# 012_AdditionalFunction.net
KiCad netlist of a schematic drawn in Altium Designer
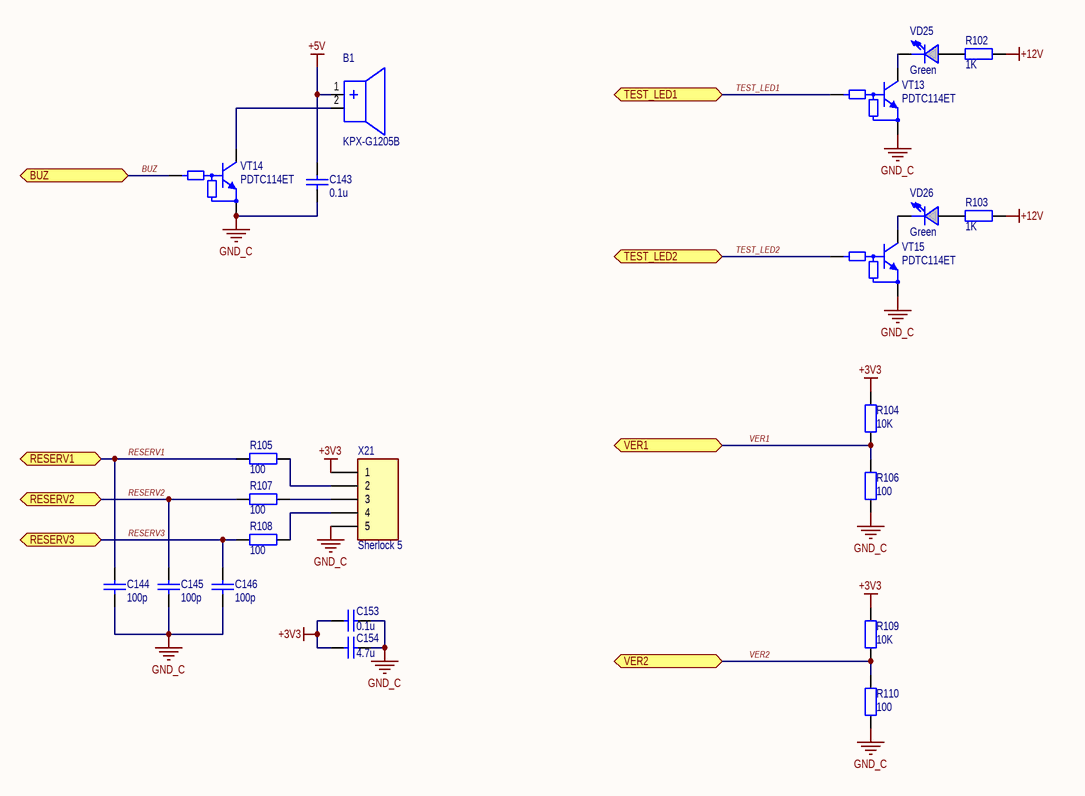
[diagram p0: 012_AdditionalFunction.SchDoc]

(export (version "E")
  (design (tool "Eeschema 10.0.6"))
  (components
    (comp (ref "B1")
      (value "KPX-G1205B")
      (footprint "mainLib:KPX-G12")
      (description "Magnetic Buzzer")
      (fields (field (name "MANUFACTURER") "KEPO"))
      (libsource (lib "mainLib") (part "KPX-G1205B"))
    )
    (comp (ref "C143")
      (value "0.1u")
      (footprint "mainLib:SMD_C_0603")
      (description "SMD C 0603 MURATA 50V 10% X7R")
      (fields (field (name "PARTNUMBER") "GRM188R71H104K") (field (name "MANUFACTURER") "MURATA"))
      (libsource (lib "mainRCLib") (part "C0603 0.1u 50V 10%"))
    )
    (comp (ref "C144")
      (value "100p")
      (footprint "mainLib:SMD_C_0603")
      (description "SMD C 0603 MURATA 100V 5% NP0")
      (fields (field (name "PARTNUMBER") "GRM1885C2A101JA01") (field (name "MANUFACTURER") "MURATA"))
      (libsource (lib "mainRCLib") (part "C0603 100p 100V 5%"))
    )
    (comp (ref "C145")
      (value "100p")
      (footprint "mainLib:SMD_C_0603")
      (description "SMD C 0603 MURATA 100V 5% NP0")
      (fields (field (name "PARTNUMBER") "GRM1885C2A101JA01") (field (name "MANUFACTURER") "MURATA"))
      (libsource (lib "mainRCLib") (part "C0603 100p 100V 5%"))
    )
    (comp (ref "C146")
      (value "100p")
      (footprint "mainLib:SMD_C_0603")
      (description "SMD C 0603 MURATA 100V 5% NP0")
      (fields (field (name "PARTNUMBER") "GRM1885C2A101JA01") (field (name "MANUFACTURER") "MURATA"))
      (libsource (lib "mainRCLib") (part "C0603 100p 100V 5%"))
    )
    (comp (ref "C153")
      (value "0.1u")
      (footprint "mainLib:SMD_C_0603")
      (description "SMD C 0603 MURATA 50V 10% X7R")
      (fields (field (name "PARTNUMBER") "GRM188R71H104K") (field (name "MANUFACTURER") "MURATA"))
      (libsource (lib "mainRCLib") (part "C0603 0.1u 50V 10%"))
    )
    (comp (ref "C154")
      (value "4.7u")
      (footprint "mainLib:SMD_C_0805")
      (description "SMD C 0805 MURATA 50V 5% NP0")
      (fields (field (name "PARTNUMBER") "GRM21BR61E475M") (field (name "MANUFACTURER") "MURATA"))
      (libsource (lib "mainRCLib") (part "C0805 4.7u 25V 20%  X5R"))
    )
    (comp (ref "R102")
      (value "1K")
      (footprint "mainLib:SMD_R_1206")
      (description "SMD R 1206 VISHAY 0.25W 200V 1% 100ppm")
      (fields (field (name "PARTNUMBER") "CRCW12061K00FK") (field (name "MANUFACTURER") "VISHAY"))
      (libsource (lib "mainRCLib") (part "R1206 1K 1%"))
    )
    (comp (ref "R103")
      (value "1K")
      (footprint "mainLib:SMD_R_1206")
      (description "SMD R 1206 VISHAY 0.25W 200V 1% 100ppm")
      (fields (field (name "PARTNUMBER") "CRCW12061K00FK") (field (name "MANUFACTURER") "VISHAY"))
      (libsource (lib "mainRCLib") (part "R1206 1K 1%"))
    )
    (comp (ref "R104")
      (value "10K")
      (footprint "SMD_R_0603")
      (description "SMD R 0603 VISHAY 0.1W 75V 1% 100ppm")
      (fields (field (name "PARTNUMBER") "CRCW060310K0FK") (field (name "MANUFACTURER") "VISHAY"))
      (libsource (lib "mainRCLib") (part "R0603 10К 1%"))
    )
    (comp (ref "R105")
      (value "100")
      (footprint "SMD_R_0603")
      (description "SMD R 0603 VISHAY 0.1W 75V 1% 100ppm")
      (fields (field (name "PARTNUMBER") "CRCW0603100RFK") (field (name "MANUFACTURER") "VISHAY"))
      (libsource (lib "mainRCLib") (part "R0603 100 1%"))
    )
    (comp (ref "R106")
      (value "100")
      (footprint "SMD_R_0603")
      (description "SMD R 0603 VISHAY 0.1W 75V 1% 100ppm")
      (fields (field (name "PARTNUMBER") "CRCW0603100RFK") (field (name "MANUFACTURER") "VISHAY"))
      (libsource (lib "") (part "R0603 100 1%_1"))
    )
    (comp (ref "R107")
      (value "100")
      (footprint "SMD_R_0603")
      (description "SMD R 0603 VISHAY 0.1W 75V 1% 100ppm")
      (fields (field (name "PARTNUMBER") "CRCW0603100RFK") (field (name "MANUFACTURER") "VISHAY"))
      (libsource (lib "mainRCLib") (part "R0603 100 1%"))
    )
    (comp (ref "R108")
      (value "100")
      (footprint "SMD_R_0603")
      (description "SMD R 0603 VISHAY 0.1W 75V 1% 100ppm")
      (fields (field (name "PARTNUMBER") "CRCW0603100RFK") (field (name "MANUFACTURER") "VISHAY"))
      (libsource (lib "mainRCLib") (part "R0603 100 1%"))
    )
    (comp (ref "R109")
      (value "10K")
      (footprint "SMD_R_0603")
      (description "SMD R 0603 VISHAY 0.1W 75V 1% 100ppm")
      (fields (field (name "PARTNUMBER") "CRCW060310K0FK") (field (name "MANUFACTURER") "VISHAY"))
      (libsource (lib "mainRCLib") (part "R0603 10К 1%"))
    )
    (comp (ref "R110")
      (value "100")
      (footprint "SMD_R_0603")
      (description "SMD R 0603 VISHAY 0.1W 75V 1% 100ppm")
      (fields (field (name "PARTNUMBER") "CRCW0603100RFK") (field (name "MANUFACTURER") "VISHAY"))
      (libsource (lib "") (part "R0603 100 1%_1"))
    )
    (comp (ref "VD25")
      (value "Green")
      (footprint "mainLib:SMD_LED_LL_Green")
      (description "LED Green SMD")
      (fields (field (name "PARTNUMBER") "LL-S172GC-2A") (field (name "MANUFACTURER") "Lucky Light"))
      (libsource (lib "mainLib") (part "LL-S172GC-2A"))
    )
    (comp (ref "VD26")
      (value "Green")
      (footprint "mainLib:SMD_LED_LL_Green")
      (description "LED Green SMD")
      (fields (field (name "PARTNUMBER") "LL-S172GC-2A") (field (name "MANUFACTURER") "Lucky Light"))
      (libsource (lib "mainLib") (part "LL-S172GC-2A"))
    )
    (comp (ref "VT13")
      (value "PDTC114ET")
      (footprint "mainLib:SOT23-3")
      (description "Digital Transistor (BRT), R1=10 kOhm, R2=10 kOhm, NPN Transistor")
      (fields (field (name "MANUFACTURER") "On Semiconductor"))
      (libsource (lib "mainLib") (part "PDTC114ET"))
    )
    (comp (ref "VT14")
      (value "PDTC114ET")
      (footprint "mainLib:SOT23-3")
      (description "Digital Transistor (BRT), R1=10 kOhm, R2=10 kOhm, NPN Transistor")
      (fields (field (name "MANUFACTURER") "On Semiconductor"))
      (libsource (lib "mainLib") (part "PDTC114ET"))
    )
    (comp (ref "VT15")
      (value "PDTC114ET")
      (footprint "mainLib:SOT23-3")
      (description "Digital Transistor (BRT), R1=10 kOhm, R2=10 kOhm, NPN Transistor")
      (fields (field (name "MANUFACTURER") "On Semiconductor"))
      (libsource (lib "mainLib") (part "PDTC114ET"))
    )
    (comp (ref "X21")
      (value "Sherlock 5")
      (footprint "mainLib:35362-0550")
      (description "Sherlock 5 Top, 2A 125V 2mm")
      (fields (field (name "PARTNUMBER") "35362-0550") (field (name "MANUFACTURER") "MOLEX"))
      (libsource (lib "mainLib") (part "35362-0550"))
    )
  )
  (nets
    (net (code "1") (name "+3V3") (class "Default")
      (node (ref "C153") (pin "1") (pinfunction "1_1") (pintype "passive"))
      (node (ref "C154") (pin "1") (pinfunction "1_1") (pintype "passive"))
      (node (ref "R104") (pin "2") (pinfunction "2_2") (pintype "passive"))
      (node (ref "R109") (pin "2") (pinfunction "2_2") (pintype "passive"))
      (node (ref "X21") (pin "1") (pinfunction "1_1") (pintype "passive"))
    )
    (net (code "2") (name "+5V") (class "Default")
      (node (ref "B1") (pin "1") (pinfunction "+_1") (pintype "passive"))
      (node (ref "C143") (pin "2") (pinfunction "2_2") (pintype "passive"))
    )
    (net (code "3") (name "+12V") (class "Default")
      (node (ref "R102") (pin "2") (pinfunction "2_2") (pintype "passive"))
      (node (ref "R103") (pin "2") (pinfunction "2_2") (pintype "passive"))
    )
    (net (code "4") (name "/BUZ") (class "Default")
      (node (ref "VT14") (pin "1") (pinfunction "B_1") (pintype "passive"))
    )
    (net (code "5") (name "/RESERV1") (class "Default")
      (node (ref "C144") (pin "2") (pinfunction "2_2") (pintype "passive"))
      (node (ref "R105") (pin "1") (pinfunction "1_1") (pintype "passive"))
    )
    (net (code "6") (name "/RESERV2") (class "Default")
      (node (ref "C145") (pin "2") (pinfunction "2_2") (pintype "passive"))
      (node (ref "R107") (pin "1") (pinfunction "1_1") (pintype "passive"))
    )
    (net (code "7") (name "/RESERV3") (class "Default")
      (node (ref "C146") (pin "2") (pinfunction "2_2") (pintype "passive"))
      (node (ref "R108") (pin "1") (pinfunction "1_1") (pintype "passive"))
    )
    (net (code "8") (name "/TEST_LED1") (class "Default")
      (node (ref "VT13") (pin "1") (pinfunction "B_1") (pintype "passive"))
    )
    (net (code "9") (name "/TEST_LED2") (class "Default")
      (node (ref "VT15") (pin "1") (pinfunction "B_1") (pintype "passive"))
    )
    (net (code "10") (name "/VER1") (class "Default")
      (node (ref "R104") (pin "1") (pinfunction "1_1") (pintype "passive"))
      (node (ref "R106") (pin "2") (pinfunction "2_2") (pintype "passive"))
    )
    (net (code "11") (name "/VER2") (class "Default")
      (node (ref "R109") (pin "1") (pinfunction "1_1") (pintype "passive"))
      (node (ref "R110") (pin "2") (pinfunction "2_2") (pintype "passive"))
    )
    (net (code "12") (name "GND_C") (class "Default")
      (node (ref "C143") (pin "1") (pinfunction "1_1") (pintype "passive"))
      (node (ref "C144") (pin "1") (pinfunction "1_1") (pintype "passive"))
      (node (ref "C145") (pin "1") (pinfunction "1_1") (pintype "passive"))
      (node (ref "C146") (pin "1") (pinfunction "1_1") (pintype "passive"))
      (node (ref "C153") (pin "2") (pinfunction "2_2") (pintype "passive"))
      (node (ref "C154") (pin "2") (pinfunction "2_2") (pintype "passive"))
      (node (ref "R106") (pin "1") (pinfunction "1_1") (pintype "passive"))
      (node (ref "R110") (pin "1") (pinfunction "1_1") (pintype "passive"))
      (node (ref "VT13") (pin "2") (pinfunction "E_2") (pintype "passive"))
      (node (ref "VT14") (pin "2") (pinfunction "E_2") (pintype "passive"))
      (node (ref "VT15") (pin "2") (pinfunction "E_2") (pintype "passive"))
      (node (ref "X21") (pin "5") (pinfunction "5_5") (pintype "passive"))
    )
    (net (code "13") (name "Net-(B1--)") (class "Default")
      (node (ref "B1") (pin "2") (pinfunction "-_2") (pintype "passive"))
      (node (ref "VT14") (pin "3") (pinfunction "C_3") (pintype "passive"))
    )
    (net (code "14") (name "Net-(R105-Pad2)") (class "Default")
      (node (ref "R105") (pin "2") (pinfunction "2_2") (pintype "passive"))
      (node (ref "X21") (pin "2") (pinfunction "2_2") (pintype "passive"))
    )
    (net (code "15") (name "Net-(R107-Pad2)") (class "Default")
      (node (ref "R107") (pin "2") (pinfunction "2_2") (pintype "passive"))
      (node (ref "X21") (pin "3") (pinfunction "3_3") (pintype "passive"))
    )
    (net (code "16") (name "Net-(R108-Pad2)") (class "Default")
      (node (ref "R108") (pin "2") (pinfunction "2_2") (pintype "passive"))
      (node (ref "X21") (pin "4") (pinfunction "4_4") (pintype "passive"))
    )
    (net (code "17") (name "Net-(VD25-ANODE)") (class "Default")
      (node (ref "R102") (pin "1") (pinfunction "1_1") (pintype "passive"))
      (node (ref "VD25") (pin "1") (pinfunction "ANODE_1") (pintype "passive"))
    )
    (net (code "18") (name "Net-(VD25-CATHODE)") (class "Default")
      (node (ref "VD25") (pin "2") (pinfunction "CATHODE_2") (pintype "passive"))
      (node (ref "VT13") (pin "3") (pinfunction "C_3") (pintype "passive"))
    )
    (net (code "19") (name "Net-(VD26-ANODE)") (class "Default")
      (node (ref "R103") (pin "1") (pinfunction "1_1") (pintype "passive"))
      (node (ref "VD26") (pin "1") (pinfunction "ANODE_1") (pintype "passive"))
    )
    (net (code "20") (name "Net-(VD26-CATHODE)") (class "Default")
      (node (ref "VD26") (pin "2") (pinfunction "CATHODE_2") (pintype "passive"))
      (node (ref "VT15") (pin "3") (pinfunction "C_3") (pintype "passive"))
    )
  )
)
